# USB_OTG.net
KiCad netlist of a schematic drawn in Altium Designer
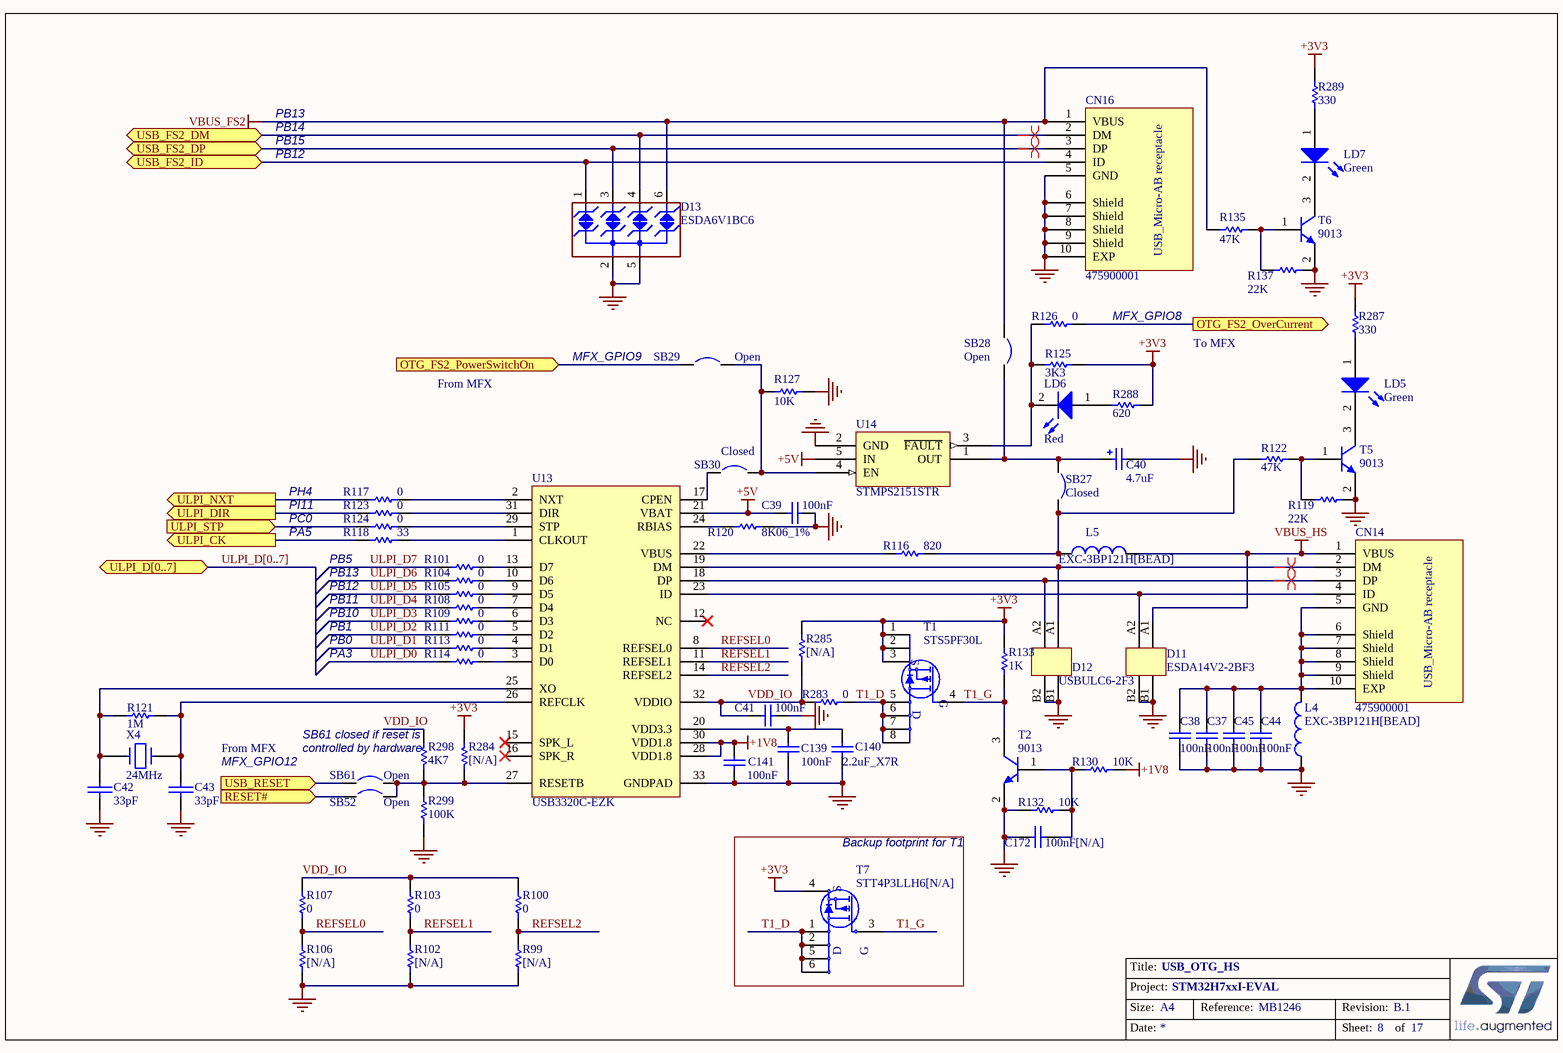
[diagram p0: USB_OTG.SchDoc]

(export (version "E")
  (design (tool "Eeschema 10.0.6"))
  (components
    (comp (ref "C37")
      (value "100nF")
      (footprint "0603C")
      (description "Capacitor")
      (fields (field (name "PUBLISHER") "Altium Limited"))
      (libsource (lib "Miscellaneous Devices") (part "Cap"))
    )
    (comp (ref "C38")
      (value "100nF")
      (footprint "0603C")
      (description "Capacitor")
      (fields (field (name "PUBLISHER") "Altium Limited"))
      (libsource (lib "Miscellaneous Devices") (part "Cap"))
    )
    (comp (ref "C39")
      (value "100nF")
      (footprint "0603C")
      (description "Capacitor")
      (fields (field (name "PUBLISHER") "Altium Limited"))
      (libsource (lib "Miscellaneous Devices") (part "Cap"))
    )
    (comp (ref "C40")
      (value "4.7uF")
      (footprint "TAN-A")
      (description "Polarized Capacitor (Radial)")
      (fields (field (name "PUBLISHER") "Altium Limited"))
      (libsource (lib "Miscellaneous Devices") (part "Cap Pol1"))
    )
    (comp (ref "C41")
      (value "100nF")
      (footprint "0603C")
      (description "Capacitor")
      (fields (field (name "PUBLISHER") "Altium Limited"))
      (libsource (lib "Miscellaneous Devices") (part "Cap"))
    )
    (comp (ref "C42")
      (value "33pF")
      (footprint "0603C")
      (description "Capacitor")
      (libsource (lib "*") (part "CAP"))
    )
    (comp (ref "C43")
      (value "33pF")
      (footprint "0603C")
      (description "Capacitor")
      (libsource (lib "*") (part "CAP"))
    )
    (comp (ref "C44")
      (value "100nF")
      (footprint "0603C")
      (description "Capacitor")
      (fields (field (name "PUBLISHER") "Altium Limited"))
      (libsource (lib "Miscellaneous Devices") (part "Cap"))
    )
    (comp (ref "C45")
      (value "100nF")
      (footprint "0603C")
      (description "Capacitor")
      (fields (field (name "PUBLISHER") "Altium Limited"))
      (libsource (lib "Miscellaneous Devices") (part "Cap"))
    )
    (comp (ref "C139")
      (value "100nF")
      (footprint "0603C")
      (description "Capacitor")
      (fields (field (name "PUBLISHER") "Altium Limited"))
      (libsource (lib "Miscellaneous Devices") (part "Cap"))
    )
    (comp (ref "C140")
      (value "2.2uF_X7R")
      (footprint "0603C")
      (description "Capacitor")
      (fields (field (name "PUBLISHER") "Altium Limited"))
      (libsource (lib "Miscellaneous Devices") (part "Cap"))
    )
    (comp (ref "C141")
      (value "100nF")
      (footprint "0603C")
      (description "Capacitor")
      (fields (field (name "PUBLISHER") "Altium Limited"))
      (libsource (lib "Miscellaneous Devices") (part "Cap"))
    )
    (comp (ref "C172")
      (value "100nF[N/A]")
      (footprint "0603C")
      (description "Capacitor,100nF,16V,X7R,10%,0402,YAGEO")
      (libsource (lib "MCD_TOOLS") (part "Cap_100nF_X7R_10%_0402"))
    )
    (comp (ref "CN14")
      (value "475900001")
      (footprint "MOLEX_47590001")
      (libsource (lib "mb1045") (part "475900001"))
    )
    (comp (ref "CN16")
      (value "475900001")
      (footprint "MOLEX_47590001")
      (libsource (lib "mb1045") (part "475900001"))
    )
    (comp (ref "D11")
      (value "ESDA14V2-2BF3")
      (footprint "BGA4_0R4_0R8X0R8")
      (libsource (lib "MB786") (part "ESDA14V2-2BF3"))
    )
    (comp (ref "D12")
      (value "USBULC6-2F3")
      (footprint "BGA4_0R4_1X1")
      (libsource (lib "MB786") (part "USBULC6-2F3"))
    )
    (comp (ref "D13")
      (value "ESDA6V1BC6")
      (footprint "STM-SMEE:SOT23-6L")
      (description "Dual Transil array for ESD protection")
      (libsource (lib "MB1137") (part "ESDA6V1BC6"))
    )
    (comp (ref "L4")
      (value "EXC-3BP121H[BEAD]")
      (footprint "0603L")
      (description "Inductor")
      (fields (field (name "PUBLISHER") "Altium Limited"))
      (libsource (lib "Miscellaneous Devices") (part "Inductor"))
    )
    (comp (ref "L5")
      (value "EXC-3BP121H[BEAD]")
      (footprint "0603L")
      (description "Inductor")
      (fields (field (name "PUBLISHER") "Altium Limited"))
      (libsource (lib "Miscellaneous Devices") (part "Inductor"))
    )
    (comp (ref "LD5")
      (value "Green")
      (footprint "0603D")
      (description "Typical RED, GREEN, YELLOW, AMBER GaAs LED")
      (fields (field (name "PUBLISHER") "Altium Limited"))
      (libsource (lib "Miscellaneous Devices") (part "LED2"))
    )
    (comp (ref "LD6")
      (value "Red")
      (footprint "0603D")
      (description "Typical RED, GREEN, YELLOW, AMBER GaAs LED")
      (fields (field (name "PUBLISHER") "Altium Limited"))
      (libsource (lib "Miscellaneous Devices") (part "LED2"))
    )
    (comp (ref "LD7")
      (value "Green")
      (footprint "0603D")
      (description "Typical RED, GREEN, YELLOW, AMBER GaAs LED")
      (fields (field (name "PUBLISHER") "Altium Limited"))
      (libsource (lib "Miscellaneous Devices") (part "LED2"))
    )
    (comp (ref "R99")
      (value "[N/A]")
      (footprint "0603R")
      (description "Resistor")
      (fields (field (name "PUBLISHER") "Altium Limited"))
      (libsource (lib "Miscellaneous Devices") (part "Res1"))
    )
    (comp (ref "R100")
      (value "0")
      (footprint "0603R")
      (description "Resistor")
      (fields (field (name "PUBLISHER") "Altium Limited"))
      (libsource (lib "Miscellaneous Devices") (part "Res1"))
    )
    (comp (ref "R101")
      (value "0")
      (footprint "0603R")
      (description "Resistor")
      (fields (field (name "PUBLISHER") "Altium Limited"))
      (libsource (lib "Miscellaneous Devices") (part "Res1"))
    )
    (comp (ref "R102")
      (value "[N/A]")
      (footprint "0603R")
      (description "Resistor")
      (fields (field (name "PUBLISHER") "Altium Limited"))
      (libsource (lib "Miscellaneous Devices") (part "Res1"))
    )
    (comp (ref "R103")
      (value "0")
      (footprint "0603R")
      (description "Resistor")
      (fields (field (name "PUBLISHER") "Altium Limited"))
      (libsource (lib "Miscellaneous Devices") (part "Res1"))
    )
    (comp (ref "R104")
      (value "0")
      (footprint "0603R")
      (description "Resistor")
      (fields (field (name "PUBLISHER") "Altium Limited"))
      (libsource (lib "Miscellaneous Devices") (part "Res1"))
    )
    (comp (ref "R105")
      (value "0")
      (footprint "0603R")
      (description "Resistor")
      (fields (field (name "PUBLISHER") "Altium Limited"))
      (libsource (lib "Miscellaneous Devices") (part "Res1"))
    )
    (comp (ref "R106")
      (value "[N/A]")
      (footprint "0603R")
      (description "Resistor")
      (fields (field (name "PUBLISHER") "Altium Limited"))
      (libsource (lib "Miscellaneous Devices") (part "Res1"))
    )
    (comp (ref "R107")
      (value "0")
      (footprint "0603R")
      (description "Resistor")
      (fields (field (name "PUBLISHER") "Altium Limited"))
      (libsource (lib "Miscellaneous Devices") (part "Res1"))
    )
    (comp (ref "R108")
      (value "0")
      (footprint "0603R")
      (description "Resistor")
      (fields (field (name "PUBLISHER") "Altium Limited"))
      (libsource (lib "Miscellaneous Devices") (part "Res1"))
    )
    (comp (ref "R109")
      (value "0")
      (footprint "0603R")
      (description "Resistor")
      (fields (field (name "PUBLISHER") "Altium Limited"))
      (libsource (lib "Miscellaneous Devices") (part "Res1"))
    )
    (comp (ref "R111")
      (value "0")
      (footprint "0603R")
      (description "Resistor")
      (fields (field (name "PUBLISHER") "Altium Limited"))
      (libsource (lib "Miscellaneous Devices") (part "Res1"))
    )
    (comp (ref "R113")
      (value "0")
      (footprint "0603R")
      (description "Resistor")
      (fields (field (name "PUBLISHER") "Altium Limited"))
      (libsource (lib "Miscellaneous Devices") (part "Res1"))
    )
    (comp (ref "R114")
      (value "0")
      (footprint "0603R")
      (description "Resistor")
      (fields (field (name "PUBLISHER") "Altium Limited"))
      (libsource (lib "Miscellaneous Devices") (part "Res1"))
    )
    (comp (ref "R116")
      (value "820")
      (footprint "0603R")
      (description "Resistor")
      (fields (field (name "PUBLISHER") "Altium Limited"))
      (libsource (lib "Miscellaneous Devices") (part "res1"))
    )
    (comp (ref "R117")
      (value "0")
      (footprint "0603R")
      (description "Resistor")
      (fields (field (name "PUBLISHER") "Altium Limited"))
      (libsource (lib "Miscellaneous Devices") (part "Res1"))
    )
    (comp (ref "R118")
      (value "33")
      (footprint "0603R")
      (description "Resistor")
      (fields (field (name "PUBLISHER") "Altium Limited"))
      (libsource (lib "Miscellaneous Devices") (part "Res1"))
    )
    (comp (ref "R119")
      (value "22K")
      (footprint "0603R")
      (description "Resistor")
      (fields (field (name "PUBLISHER") "Altium Limited"))
      (libsource (lib "Miscellaneous Devices") (part "res1"))
    )
    (comp (ref "R120")
      (value "8K06_1%")
      (footprint "0603R")
      (description "Resistor,8K06,0402,1%,YAGEO")
      (libsource (lib "MCD_TOOLS") (part "Res_8K06_1%_0402"))
    )
    (comp (ref "R121")
      (value "1M")
      (footprint "0603R")
      (description "Resistor")
      (fields (field (name "PUBLISHER") "Altium Limited"))
      (libsource (lib "Miscellaneous Devices") (part "Res1"))
    )
    (comp (ref "R122")
      (value "47K")
      (footprint "0603R")
      (description "Resistor")
      (fields (field (name "PUBLISHER") "Altium Limited"))
      (libsource (lib "Miscellaneous Devices") (part "res1"))
    )
    (comp (ref "R123")
      (value "0")
      (footprint "0603R")
      (description "Resistor")
      (fields (field (name "PUBLISHER") "Altium Limited"))
      (libsource (lib "Miscellaneous Devices") (part "Res1"))
    )
    (comp (ref "R124")
      (value "0")
      (footprint "0603R")
      (description "Resistor")
      (fields (field (name "PUBLISHER") "Altium Limited"))
      (libsource (lib "Miscellaneous Devices") (part "Res1"))
    )
    (comp (ref "R125")
      (value "3K3")
      (footprint "0603R")
      (description "Resistor")
      (fields (field (name "PUBLISHER") "Altium Limited"))
      (libsource (lib "Miscellaneous Devices") (part "res1"))
    )
    (comp (ref "R126")
      (value "0")
      (footprint "0603R")
      (description "Resistor")
      (fields (field (name "PUBLISHER") "Altium Limited"))
      (libsource (lib "Miscellaneous Devices") (part "Res1"))
    )
    (comp (ref "R127")
      (value "10K")
      (footprint "0603R")
      (description "Resistor")
      (fields (field (name "PUBLISHER") "Altium Limited"))
      (libsource (lib "Miscellaneous Devices") (part "res1"))
    )
    (comp (ref "R130")
      (value "10K")
      (footprint "0603R")
      (description "Resistor")
      (fields (field (name "PUBLISHER") "Altium Limited"))
      (libsource (lib "Miscellaneous Devices") (part "res1"))
    )
    (comp (ref "R132")
      (value "10K")
      (footprint "0603R")
      (description "Resistor")
      (fields (field (name "PUBLISHER") "Altium Limited"))
      (libsource (lib "Miscellaneous Devices") (part "res1"))
    )
    (comp (ref "R133")
      (value "1K")
      (footprint "0603R")
      (description "Resistor")
      (fields (field (name "PUBLISHER") "Altium Limited"))
      (libsource (lib "Miscellaneous Devices") (part "res1"))
    )
    (comp (ref "R135")
      (value "47K")
      (footprint "0603R")
      (description "Resistor")
      (fields (field (name "PUBLISHER") "Altium Limited"))
      (libsource (lib "Miscellaneous Devices") (part "res1"))
    )
    (comp (ref "R137")
      (value "22K")
      (footprint "0603R")
      (description "Resistor")
      (fields (field (name "PUBLISHER") "Altium Limited"))
      (libsource (lib "Miscellaneous Devices") (part "res1"))
    )
    (comp (ref "R283")
      (value "0")
      (footprint "0603R")
      (description "Resistor")
      (fields (field (name "PUBLISHER") "Altium Limited"))
      (libsource (lib "Miscellaneous Devices") (part "Res1"))
    )
    (comp (ref "R284")
      (value "[N/A]")
      (footprint "0603R")
      (description "Resistor")
      (fields (field (name "PUBLISHER") "Altium Limited"))
      (libsource (lib "*") (part "Res1"))
    )
    (comp (ref "R285")
      (value "[N/A]")
      (footprint "0603R")
      (description "Resistor")
      (fields (field (name "PUBLISHER") "Altium Limited"))
      (libsource (lib "Miscellaneous Devices") (part "Res1"))
    )
    (comp (ref "R287")
      (value "330")
      (footprint "0603R")
      (description "Resistor")
      (fields (field (name "PUBLISHER") "Altium Limited"))
      (libsource (lib "Miscellaneous Devices") (part "res1"))
    )
    (comp (ref "R288")
      (value "620")
      (footprint "0603R")
      (description "Resistor")
      (fields (field (name "PUBLISHER") "Altium Limited"))
      (libsource (lib "Miscellaneous Devices") (part "Res1"))
    )
    (comp (ref "R289")
      (value "330")
      (footprint "0603R")
      (description "Resistor")
      (fields (field (name "PUBLISHER") "Altium Limited"))
      (libsource (lib "Miscellaneous Devices") (part "res1"))
    )
    (comp (ref "R298")
      (value "4K7")
      (footprint "0603R")
      (description "Resistor")
      (fields (field (name "PUBLISHER") "Altium Limited"))
      (libsource (lib "*") (part "Res1"))
    )
    (comp (ref "R299")
      (value "100K")
      (footprint "0603R")
      (description "Resistor 0402 or 0603 or 0805")
      (libsource (lib "") (part "Res1_1"))
    )
    (comp (ref "SB27")
      (value "Closed")
      (footprint "SB_0603")
      (description "Circuit Breaker")
      (fields (field (name "PUBLISHER") "Altium Limited"))
      (libsource (lib "MB1165") (part "Circuit Breaker_close"))
    )
    (comp (ref "SB28")
      (value "Open")
      (footprint "SB_0603")
      (description "Circuit Breaker")
      (fields (field (name "PUBLISHER") "Altium Limited"))
      (libsource (lib "MB1165") (part "Circuit Breaker"))
    )
    (comp (ref "SB29")
      (value "Open")
      (footprint "SB_0603")
      (description "Circuit Breaker")
      (fields (field (name "PUBLISHER") "Altium Limited"))
      (libsource (lib "MB1165") (part "Circuit Breaker"))
    )
    (comp (ref "SB30")
      (value "Closed")
      (footprint "SB_0603")
      (description "Circuit Breaker")
      (fields (field (name "PUBLISHER") "Altium Limited"))
      (libsource (lib "MB1165") (part "Circuit Breaker_close"))
    )
    (comp (ref "SB52")
      (value "Open")
      (footprint "SB_0603")
      (description "Circuit Breaker")
      (fields (field (name "PUBLISHER") "Altium Limited"))
      (libsource (lib "MB1165") (part "Circuit Breaker"))
    )
    (comp (ref "SB61")
      (value "Open")
      (footprint "SB_0603")
      (description "Circuit Breaker")
      (fields (field (name "PUBLISHER") "Altium Limited"))
      (libsource (lib "MB1165") (part "Circuit Breaker"))
    )
    (comp (ref "T1")
      (value "STS5PF30L")
      (footprint "SOIC8_1R27_4R9X6")
      (libsource (lib "Nucleo_64") (part "STS7PF30L"))
    )
    (comp (ref "T2")
      (value "9013")
      (footprint "SOT-23")
      (description "NPN Bipolar Transistor")
      (fields (field (name "PUBLISHER") "Altium Limited"))
      (libsource (lib "MB1167") (part "NPN"))
    )
    (comp (ref "T5")
      (value "9013")
      (footprint "SOT-23")
      (description "NPN Bipolar Transistor")
      (fields (field (name "PUBLISHER") "Altium Limited"))
      (libsource (lib "MB1167") (part "NPN"))
    )
    (comp (ref "T6")
      (value "9013")
      (footprint "SOT-23")
      (description "NPN Bipolar Transistor")
      (fields (field (name "PUBLISHER") "Altium Limited"))
      (libsource (lib "MB1167") (part "NPN"))
    )
    (comp (ref "T7")
      (value "STT4P3LLH6[N/A]")
      (footprint "SOT23-6L")
      (description "STripFET VII DeepGATE Power MOSFET, P-CHANNEL 20 V, 0.0146, 7 A - SOT23-6L")
      (libsource (lib "MCD_TOOLS") (part "STT7P2UH7"))
    )
    (comp (ref "U13")
      (value "USB3320C-EZK")
      (footprint "QFN32_0R5_5X5")
      (description "USB3320C, Hi-Speed USB Host, Device or OTG PHY with ULPI Low Pin Interface")
      (libsource (lib "MCD_TOOLS") (part "USB3320C-EZK"))
    )
    (comp (ref "U14")
      (value "STMPS2151STR")
      (footprint "SOT23-5")
      (libsource (lib "mb1045") (part "STMPS2141STR"))
    )
    (comp (ref "X4")
      (value "24MHz")
      (footprint "XTAL1")
      (description "Crystal")
      (libsource (lib "*") (part "CRYSTAL"))
    )
  )
  (nets
    (net (code "1") (name "+1V8") (class "Default")
      (node (ref "C141") (pin "1") (pinfunction "1_1") (pintype "passive"))
      (node (ref "R130") (pin "1") (pinfunction "1_1") (pintype "passive"))
      (node (ref "U13") (pin "28") (pinfunction "VDD1.8_28") (pintype "passive"))
      (node (ref "U13") (pin "30") (pinfunction "VDD1.8_30") (pintype "passive"))
    )
    (net (code "2") (name "+3V3") (class "Default")
      (node (ref "R125") (pin "1") (pinfunction "1_1") (pintype "passive"))
      (node (ref "R133") (pin "2") (pinfunction "2_2") (pintype "passive"))
      (node (ref "R284") (pin "2") (pinfunction "2_2") (pintype "passive"))
      (node (ref "R285") (pin "1") (pinfunction "1_1") (pintype "passive"))
      (node (ref "R287") (pin "2") (pinfunction "2_2") (pintype "passive"))
      (node (ref "R288") (pin "2") (pinfunction "2_2") (pintype "passive"))
      (node (ref "R289") (pin "2") (pinfunction "2_2") (pintype "passive"))
      (node (ref "T1") (pin "1") (pinfunction "S_1") (pintype "passive"))
      (node (ref "T1") (pin "2") (pinfunction "S_2") (pintype "passive"))
      (node (ref "T1") (pin "3") (pinfunction "S_3") (pintype "passive"))
      (node (ref "T7") (pin "4") (pinfunction "S_4") (pintype "passive"))
    )
    (net (code "3") (name "+5V") (class "Default")
      (node (ref "C39") (pin "1") (pinfunction "1_1") (pintype "passive"))
      (node (ref "U13") (pin "21") (pinfunction "VBAT_21") (pintype "passive"))
      (node (ref "U14") (pin "5") (pinfunction "IN_5") (pintype "passive"))
    )
    (net (code "4") (name "/OTG_FS2_OverCurrent") (class "Default")
      (node (ref "R126") (pin "1") (pinfunction "1_1") (pintype "passive"))
    )
    (net (code "5") (name "/OTG_FS2_PowerSwitchOn") (class "Default")
      (node (ref "SB29") (pin "1") (pinfunction "1_1") (pintype "passive"))
    )
    (net (code "6") (name "/REFSEL0") (class "Default")
      (node (ref "R106") (pin "2") (pinfunction "2_2") (pintype "passive"))
      (node (ref "R107") (pin "1") (pinfunction "1_1") (pintype "passive"))
      (node (ref "U13") (pin "8") (pinfunction "REFSEL0_8") (pintype "passive"))
    )
    (net (code "7") (name "/REFSEL1") (class "Default")
      (node (ref "R102") (pin "2") (pinfunction "2_2") (pintype "passive"))
      (node (ref "R103") (pin "1") (pinfunction "1_1") (pintype "passive"))
      (node (ref "U13") (pin "11") (pinfunction "REFSEL1_11") (pintype "passive"))
    )
    (net (code "8") (name "/REFSEL2") (class "Default")
      (node (ref "R100") (pin "1") (pinfunction "1_1") (pintype "passive"))
      (node (ref "R99") (pin "2") (pinfunction "2_2") (pintype "passive"))
      (node (ref "U13") (pin "14") (pinfunction "REFSEL2_14") (pintype "passive"))
    )
    (net (code "9") (name "/RESET#") (class "Default")
      (node (ref "SB52") (pin "1") (pinfunction "1_1") (pintype "passive"))
    )
    (net (code "10") (name "/T1_D") (class "Default")
      (node (ref "R283") (pin "1") (pinfunction "1_1") (pintype "passive"))
      (node (ref "T1") (pin "5") (pinfunction "D_5") (pintype "passive"))
      (node (ref "T1") (pin "6") (pinfunction "D_6") (pintype "passive"))
      (node (ref "T1") (pin "7") (pinfunction "D_7") (pintype "passive"))
      (node (ref "T1") (pin "8") (pinfunction "D_8") (pintype "passive"))
      (node (ref "T7") (pin "1") (pinfunction "S_1") (pintype "passive"))
      (node (ref "T7") (pin "2") (pinfunction "S_2") (pintype "passive"))
      (node (ref "T7") (pin "5") (pinfunction "D_5") (pintype "passive"))
      (node (ref "T7") (pin "6") (pinfunction "D_6") (pintype "passive"))
    )
    (net (code "11") (name "/T1_G") (class "Default")
      (node (ref "R133") (pin "1") (pinfunction "1_1") (pintype "passive"))
      (node (ref "T1") (pin "4") (pinfunction "G_4") (pintype "passive"))
      (node (ref "T2") (pin "3") (pinfunction "C_3") (pintype "passive"))
      (node (ref "T7") (pin "3") (pinfunction "G_3") (pintype "passive"))
    )
    (net (code "12") (name "/ULPI_CK") (class "Default")
      (node (ref "R118") (pin "2") (pinfunction "2_2") (pintype "passive"))
    )
    (net (code "13") (name "/ULPI_D0") (class "Default")
      (node (ref "R114") (pin "2") (pinfunction "2_2") (pintype "passive"))
    )
    (net (code "14") (name "/ULPI_D1") (class "Default")
      (node (ref "R113") (pin "2") (pinfunction "2_2") (pintype "passive"))
    )
    (net (code "15") (name "/ULPI_D2") (class "Default")
      (node (ref "R111") (pin "2") (pinfunction "2_2") (pintype "passive"))
    )
    (net (code "16") (name "/ULPI_D3") (class "Default")
      (node (ref "R109") (pin "2") (pinfunction "2_2") (pintype "passive"))
    )
    (net (code "17") (name "/ULPI_D4") (class "Default")
      (node (ref "R108") (pin "2") (pinfunction "2_2") (pintype "passive"))
    )
    (net (code "18") (name "/ULPI_D5") (class "Default")
      (node (ref "R105") (pin "2") (pinfunction "2_2") (pintype "passive"))
    )
    (net (code "19") (name "/ULPI_D6") (class "Default")
      (node (ref "R104") (pin "2") (pinfunction "2_2") (pintype "passive"))
    )
    (net (code "20") (name "/ULPI_D7") (class "Default")
      (node (ref "R101") (pin "2") (pinfunction "2_2") (pintype "passive"))
    )
    (net (code "21") (name "/ULPI_DIR") (class "Default")
      (node (ref "R123") (pin "2") (pinfunction "2_2") (pintype "passive"))
    )
    (net (code "23") (name "/ULPI_NXT") (class "Default")
      (node (ref "R117") (pin "2") (pinfunction "2_2") (pintype "passive"))
    )
    (net (code "24") (name "/ULPI_STP") (class "Default")
      (node (ref "R124") (pin "2") (pinfunction "2_2") (pintype "passive"))
    )
    (net (code "25") (name "/USB_FS2_DM") (class "Default")
      (node (ref "CN16") (pin "2") (pinfunction "DM_2") (pintype "passive"))
      (node (ref "D13") (pin "4") (pinfunction "IO3_4") (pintype "passive"))
    )
    (net (code "26") (name "/USB_FS2_DP") (class "Default")
      (node (ref "CN16") (pin "3") (pinfunction "DP_3") (pintype "passive"))
      (node (ref "D13") (pin "3") (pinfunction "GND_3") (pintype "passive"))
    )
    (net (code "27") (name "/USB_FS2_ID") (class "Default")
      (node (ref "CN16") (pin "4") (pinfunction "ID_4") (pintype "passive"))
      (node (ref "D13") (pin "1") (pinfunction "IO1_1") (pintype "passive"))
    )
    (net (code "28") (name "/USB_RESET") (class "Default")
      (node (ref "SB61") (pin "1") (pinfunction "1_1") (pintype "passive"))
    )
    (net (code "29") (name "/VDD_IO") (class "Default")
      (node (ref "C41") (pin "1") (pinfunction "1_1") (pintype "passive"))
      (node (ref "R100") (pin "2") (pinfunction "2_2") (pintype "passive"))
      (node (ref "R103") (pin "2") (pinfunction "2_2") (pintype "passive"))
      (node (ref "R107") (pin "2") (pinfunction "2_2") (pintype "passive"))
      (node (ref "R283") (pin "2") (pinfunction "2_2") (pintype "passive"))
      (node (ref "R285") (pin "2") (pinfunction "2_2") (pintype "passive"))
      (node (ref "R298") (pin "2") (pinfunction "2_2") (pintype "passive"))
      (node (ref "U13") (pin "32") (pinfunction "VDDIO_32") (pintype "passive"))
    )
    (net (code "30") (name "GND") (class "Default")
      (node (ref "C139") (pin "2") (pinfunction "2_2") (pintype "passive"))
      (node (ref "C140") (pin "1") (pinfunction "1_1") (pintype "passive"))
      (node (ref "C141") (pin "2") (pinfunction "2_2") (pintype "passive"))
      (node (ref "C172") (pin "2") (pinfunction "2_2") (pintype "passive"))
      (node (ref "C37") (pin "2") (pinfunction "2_2") (pintype "passive"))
      (node (ref "C38") (pin "2") (pinfunction "2_2") (pintype "passive"))
      (node (ref "C39") (pin "2") (pinfunction "2_2") (pintype "passive"))
      (node (ref "C40") (pin "2") (pinfunction "2_2") (pintype "passive"))
      (node (ref "C41") (pin "2") (pinfunction "2_2") (pintype "passive"))
      (node (ref "C42") (pin "2") (pinfunction "2_2") (pintype "passive"))
      (node (ref "C43") (pin "2") (pinfunction "2_2") (pintype "passive"))
      (node (ref "C44") (pin "2") (pinfunction "2_2") (pintype "passive"))
      (node (ref "C45") (pin "2") (pinfunction "2_2") (pintype "passive"))
      (node (ref "CN16") (pin "10") (pinfunction "EXP_10") (pintype "passive"))
      (node (ref "CN16") (pin "5") (pinfunction "GND_5") (pintype "passive"))
      (node (ref "CN16") (pin "6") (pinfunction "Shield_6") (pintype "passive"))
      (node (ref "CN16") (pin "7") (pinfunction "Shield_7") (pintype "passive"))
      (node (ref "CN16") (pin "8") (pinfunction "Shield_8") (pintype "passive"))
      (node (ref "CN16") (pin "9") (pinfunction "Shield_9") (pintype "passive"))
      (node (ref "D11") (pin "B1") (pintype "passive"))
      (node (ref "D11") (pin "B2") (pintype "passive"))
      (node (ref "D12") (pin "B1") (pintype "passive"))
      (node (ref "D12") (pin "B2") (pintype "passive"))
      (node (ref "D13") (pin "2") (pinfunction "IO2_2") (pintype "passive"))
      (node (ref "D13") (pin "5") (pinfunction "IO4_5") (pintype "passive"))
      (node (ref "L4") (pin "1") (pinfunction "1_1") (pintype "passive"))
      (node (ref "R102") (pin "1") (pinfunction "1_1") (pintype "passive"))
      (node (ref "R106") (pin "1") (pinfunction "1_1") (pintype "passive"))
      (node (ref "R119") (pin "1") (pinfunction "1_1") (pintype "passive"))
      (node (ref "R120") (pin "2") (pinfunction "2_2") (pintype "passive"))
      (node (ref "R127") (pin "1") (pinfunction "1_1") (pintype "passive"))
      (node (ref "R132") (pin "2") (pinfunction "2_2") (pintype "passive"))
      (node (ref "R137") (pin "1") (pinfunction "1_1") (pintype "passive"))
      (node (ref "R299") (pin "1") (pinfunction "1_1") (pintype "passive"))
      (node (ref "R99") (pin "1") (pinfunction "1_1") (pintype "passive"))
      (node (ref "T2") (pin "2") (pinfunction "E_2") (pintype "passive"))
      (node (ref "T5") (pin "2") (pinfunction "E_2") (pintype "passive"))
      (node (ref "T6") (pin "2") (pinfunction "E_2") (pintype "passive"))
      (node (ref "U13") (pin "33") (pinfunction "GNDPAD_33") (pintype "passive"))
      (node (ref "U14") (pin "2") (pinfunction "GND_2") (pintype "passive"))
    )
    (net (code "31") (name "Net-(CN14-DM)") (class "Default")
      (node (ref "CN14") (pin "2") (pinfunction "DM_2") (pintype "passive"))
      (node (ref "D12") (pin "A1") (pintype "passive"))
      (node (ref "U13") (pin "19") (pinfunction "DM_19") (pintype "passive"))
    )
    (net (code "32") (name "Net-(CN14-DP)") (class "Default")
      (node (ref "CN14") (pin "3") (pinfunction "DP_3") (pintype "passive"))
      (node (ref "D12") (pin "A2") (pintype "passive"))
      (node (ref "U13") (pin "18") (pinfunction "DP_18") (pintype "passive"))
    )
    (net (code "33") (name "Net-(CN14-EXP)") (class "Default")
      (node (ref "C37") (pin "1") (pinfunction "1_1") (pintype "passive"))
      (node (ref "C38") (pin "1") (pinfunction "1_1") (pintype "passive"))
      (node (ref "C44") (pin "1") (pinfunction "1_1") (pintype "passive"))
      (node (ref "C45") (pin "1") (pinfunction "1_1") (pintype "passive"))
      (node (ref "CN14") (pin "10") (pinfunction "EXP_10") (pintype "passive"))
      (node (ref "CN14") (pin "5") (pinfunction "GND_5") (pintype "passive"))
      (node (ref "CN14") (pin "6") (pinfunction "Shield_6") (pintype "passive"))
      (node (ref "CN14") (pin "7") (pinfunction "Shield_7") (pintype "passive"))
      (node (ref "CN14") (pin "8") (pinfunction "Shield_8") (pintype "passive"))
      (node (ref "CN14") (pin "9") (pinfunction "Shield_9") (pintype "passive"))
      (node (ref "L4") (pin "2") (pinfunction "2_2") (pintype "passive"))
    )
    (net (code "34") (name "Net-(CN14-ID)") (class "Default")
      (node (ref "CN14") (pin "4") (pinfunction "ID_4") (pintype "passive"))
      (node (ref "D11") (pin "A2") (pintype "passive"))
      (node (ref "U13") (pin "23") (pinfunction "ID_23") (pintype "passive"))
    )
    (net (code "35") (name "Net-(L5-Pad1)") (class "Default")
      (node (ref "L5") (pin "1") (pinfunction "1_1") (pintype "passive"))
      (node (ref "R116") (pin "2") (pinfunction "2_2") (pintype "passive"))
      (node (ref "R122") (pin "2") (pinfunction "2_2") (pintype "passive"))
      (node (ref "SB27") (pin "2") (pinfunction "2_2") (pintype "passive"))
    )
    (net (code "36") (name "Net-(LD5-A)") (class "Default")
      (node (ref "LD5") (pin "1") (pinfunction "A_1") (pintype "passive"))
      (node (ref "R287") (pin "1") (pinfunction "1_1") (pintype "passive"))
    )
    (net (code "37") (name "Net-(LD5-K)") (class "Default")
      (node (ref "LD5") (pin "2") (pinfunction "K_2") (pintype "passive"))
      (node (ref "T5") (pin "3") (pinfunction "C_3") (pintype "passive"))
    )
    (net (code "38") (name "Net-(LD6-A)") (class "Default")
      (node (ref "LD6") (pin "1") (pinfunction "A_1") (pintype "passive"))
      (node (ref "R288") (pin "1") (pinfunction "1_1") (pintype "passive"))
    )
    (net (code "39") (name "Net-(LD6-K)") (class "Default")
      (node (ref "LD6") (pin "2") (pinfunction "K_2") (pintype "passive"))
      (node (ref "R125") (pin "2") (pinfunction "2_2") (pintype "passive"))
      (node (ref "R126") (pin "2") (pinfunction "2_2") (pintype "passive"))
      (node (ref "U14") (pin "3") (pinfunction "~{FAULT}_3") (pintype "output"))
    )
    (net (code "40") (name "Net-(LD7-A)") (class "Default")
      (node (ref "LD7") (pin "1") (pinfunction "A_1") (pintype "passive"))
      (node (ref "R289") (pin "1") (pinfunction "1_1") (pintype "passive"))
    )
    (net (code "41") (name "Net-(LD7-K)") (class "Default")
      (node (ref "LD7") (pin "2") (pinfunction "K_2") (pintype "passive"))
      (node (ref "T6") (pin "3") (pinfunction "C_3") (pintype "passive"))
    )
    (net (code "42") (name "Net-(T2-B)") (class "Default")
      (node (ref "C172") (pin "1") (pinfunction "1_1") (pintype "passive"))
      (node (ref "R130") (pin "2") (pinfunction "2_2") (pintype "passive"))
      (node (ref "R132") (pin "1") (pinfunction "1_1") (pintype "passive"))
      (node (ref "T2") (pin "1") (pinfunction "B_1") (pintype "passive"))
    )
    (net (code "43") (name "Net-(T5-B)") (class "Default")
      (node (ref "R119") (pin "2") (pinfunction "2_2") (pintype "passive"))
      (node (ref "R122") (pin "1") (pinfunction "1_1") (pintype "passive"))
      (node (ref "T5") (pin "1") (pinfunction "B_1") (pintype "passive"))
    )
    (net (code "44") (name "Net-(T6-B)") (class "Default")
      (node (ref "R135") (pin "2") (pinfunction "2_2") (pintype "passive"))
      (node (ref "R137") (pin "2") (pinfunction "2_2") (pintype "passive"))
      (node (ref "T6") (pin "1") (pinfunction "B_1") (pintype "passive"))
    )
    (net (code "45") (name "Net-(U13-CLKOUT)") (class "Default")
      (node (ref "R118") (pin "1") (pinfunction "1_1") (pintype "passive"))
      (node (ref "U13") (pin "1") (pinfunction "CLKOUT_1") (pintype "passive"))
    )
    (net (code "46") (name "Net-(U13-CPEN)") (class "Default")
      (node (ref "SB30") (pin "1") (pinfunction "1_1") (pintype "passive"))
      (node (ref "U13") (pin "17") (pinfunction "CPEN_17") (pintype "passive"))
    )
    (net (code "47") (name "Net-(U13-D0)") (class "Default")
      (node (ref "R114") (pin "1") (pinfunction "1_1") (pintype "passive"))
      (node (ref "U13") (pin "3") (pinfunction "D0_3") (pintype "passive"))
    )
    (net (code "48") (name "Net-(U13-D1)") (class "Default")
      (node (ref "R113") (pin "1") (pinfunction "1_1") (pintype "passive"))
      (node (ref "U13") (pin "4") (pinfunction "D1_4") (pintype "passive"))
    )
    (net (code "49") (name "Net-(U13-D2)") (class "Default")
      (node (ref "R111") (pin "1") (pinfunction "1_1") (pintype "passive"))
      (node (ref "U13") (pin "5") (pinfunction "D2_5") (pintype "passive"))
    )
    (net (code "50") (name "Net-(U13-D3)") (class "Default")
      (node (ref "R109") (pin "1") (pinfunction "1_1") (pintype "passive"))
      (node (ref "U13") (pin "6") (pinfunction "D3_6") (pintype "passive"))
    )
    (net (code "51") (name "Net-(U13-D4)") (class "Default")
      (node (ref "R108") (pin "1") (pinfunction "1_1") (pintype "passive"))
      (node (ref "U13") (pin "7") (pinfunction "D4_7") (pintype "passive"))
    )
    (net (code "52") (name "Net-(U13-D5)") (class "Default")
      (node (ref "R105") (pin "1") (pinfunction "1_1") (pintype "passive"))
      (node (ref "U13") (pin "9") (pinfunction "D5_9") (pintype "passive"))
    )
    (net (code "53") (name "Net-(U13-D6)") (class "Default")
      (node (ref "R104") (pin "1") (pinfunction "1_1") (pintype "passive"))
      (node (ref "U13") (pin "10") (pinfunction "D6_10") (pintype "passive"))
    )
    (net (code "54") (name "Net-(U13-D7)") (class "Default")
      (node (ref "R101") (pin "1") (pinfunction "1_1") (pintype "passive"))
      (node (ref "U13") (pin "13") (pinfunction "D7_13") (pintype "passive"))
    )
    (net (code "55") (name "Net-(U13-DIR)") (class "Default")
      (node (ref "R123") (pin "1") (pinfunction "1_1") (pintype "passive"))
      (node (ref "U13") (pin "31") (pinfunction "DIR_31") (pintype "passive"))
    )
    (net (code "56") (name "Net-(U13-NXT)") (class "Default")
      (node (ref "R117") (pin "1") (pinfunction "1_1") (pintype "passive"))
      (node (ref "U13") (pin "2") (pinfunction "NXT_2") (pintype "passive"))
    )
    (net (code "57") (name "Net-(U13-RBIAS)") (class "Default")
      (node (ref "R120") (pin "1") (pinfunction "1_1") (pintype "passive"))
      (node (ref "U13") (pin "24") (pinfunction "RBIAS_24") (pintype "passive"))
    )
    (net (code "58") (name "Net-(U13-REFCLK)") (class "Default")
      (node (ref "C43") (pin "1") (pinfunction "1_1") (pintype "passive"))
      (node (ref "R121") (pin "2") (pinfunction "2_2") (pintype "passive"))
      (node (ref "U13") (pin "26") (pinfunction "REFCLK_26") (pintype "passive"))
      (node (ref "X4") (pin "1") (pinfunction "1_1") (pintype "passive"))
    )
    (net (code "59") (name "Net-(U13-RESETB)") (class "Default")
      (node (ref "R284") (pin "1") (pinfunction "1_1") (pintype "passive"))
      (node (ref "R298") (pin "1") (pinfunction "1_1") (pintype "passive"))
      (node (ref "R299") (pin "2") (pinfunction "2_2") (pintype "passive"))
      (node (ref "SB52") (pin "2") (pinfunction "2_2") (pintype "passive"))
      (node (ref "SB61") (pin "2") (pinfunction "2_2") (pintype "passive"))
      (node (ref "U13") (pin "27") (pinfunction "RESETB_27") (pintype "passive"))
    )
    (net (code "60") (name "Net-(U13-STP)") (class "Default")
      (node (ref "R124") (pin "1") (pinfunction "1_1") (pintype "passive"))
      (node (ref "U13") (pin "29") (pinfunction "STP_29") (pintype "passive"))
    )
    (net (code "61") (name "Net-(U13-VBUS)") (class "Default")
      (node (ref "R116") (pin "1") (pinfunction "1_1") (pintype "passive"))
      (node (ref "U13") (pin "22") (pinfunction "VBUS_22") (pintype "passive"))
    )
    (net (code "62") (name "Net-(U13-VDD3.3)") (class "Default")
      (node (ref "C139") (pin "1") (pinfunction "1_1") (pintype "passive"))
      (node (ref "C140") (pin "2") (pinfunction "2_2") (pintype "passive"))
      (node (ref "U13") (pin "20") (pinfunction "VDD3.3_20") (pintype "passive"))
    )
    (net (code "63") (name "Net-(U13-XO)") (class "Default")
      (node (ref "C42") (pin "1") (pinfunction "1_1") (pintype "passive"))
      (node (ref "R121") (pin "1") (pinfunction "1_1") (pintype "passive"))
      (node (ref "U13") (pin "25") (pinfunction "XO_25") (pintype "passive"))
      (node (ref "X4") (pin "2") (pinfunction "2_2") (pintype "passive"))
    )
    (net (code "64") (name "Net-(U14-EN)") (class "Default")
      (node (ref "R127") (pin "2") (pinfunction "2_2") (pintype "passive"))
      (node (ref "SB29") (pin "2") (pinfunction "2_2") (pintype "passive"))
      (node (ref "SB30") (pin "2") (pinfunction "2_2") (pintype "passive"))
      (node (ref "U14") (pin "4") (pinfunction "EN_4") (pintype "input"))
    )
    (net (code "65") (name "Net-(U14-OUT)") (class "Default")
      (node (ref "C40") (pin "1") (pinfunction "1_1") (pintype "passive"))
      (node (ref "SB27") (pin "1") (pinfunction "1_1") (pintype "passive"))
      (node (ref "SB28") (pin "2") (pinfunction "2_2") (pintype "passive"))
      (node (ref "U14") (pin "1") (pinfunction "OUT_1") (pintype "passive"))
    )
    (net (code "66") (name "VBUS_FS2") (class "Default")
      (node (ref "CN16") (pin "1") (pinfunction "VBUS_1") (pintype "passive"))
      (node (ref "D13") (pin "6") (pinfunction "NC_6") (pintype "passive"))
      (node (ref "R135") (pin "1") (pinfunction "1_1") (pintype "passive"))
      (node (ref "SB28") (pin "1") (pinfunction "1_1") (pintype "passive"))
    )
    (net (code "67") (name "VBUS_HS") (class "Default")
      (node (ref "CN14") (pin "1") (pinfunction "VBUS_1") (pintype "passive"))
      (node (ref "D11") (pin "A1") (pintype "passive"))
      (node (ref "L5") (pin "2") (pinfunction "2_2") (pintype "passive"))
    )
    (net (code "68") (name "unconnected-(U13-NC-Pad12)") (class "Default")
      (node (ref "U13") (pin "12") (pinfunction "NC_12") (pintype "passive+no_connect"))
    )
    (net (code "69") (name "unconnected-(U13-SPK_L-Pad15)") (class "Default")
      (node (ref "U13") (pin "15") (pinfunction "SPK_L_15") (pintype "passive+no_connect"))
    )
    (net (code "70") (name "unconnected-(U13-SPK_R-Pad16)") (class "Default")
      (node (ref "U13") (pin "16") (pinfunction "SPK_R_16") (pintype "passive+no_connect"))
    )
  )
)
